# fp_banana.net
KiCad netlist of a schematic drawn in EAGLE
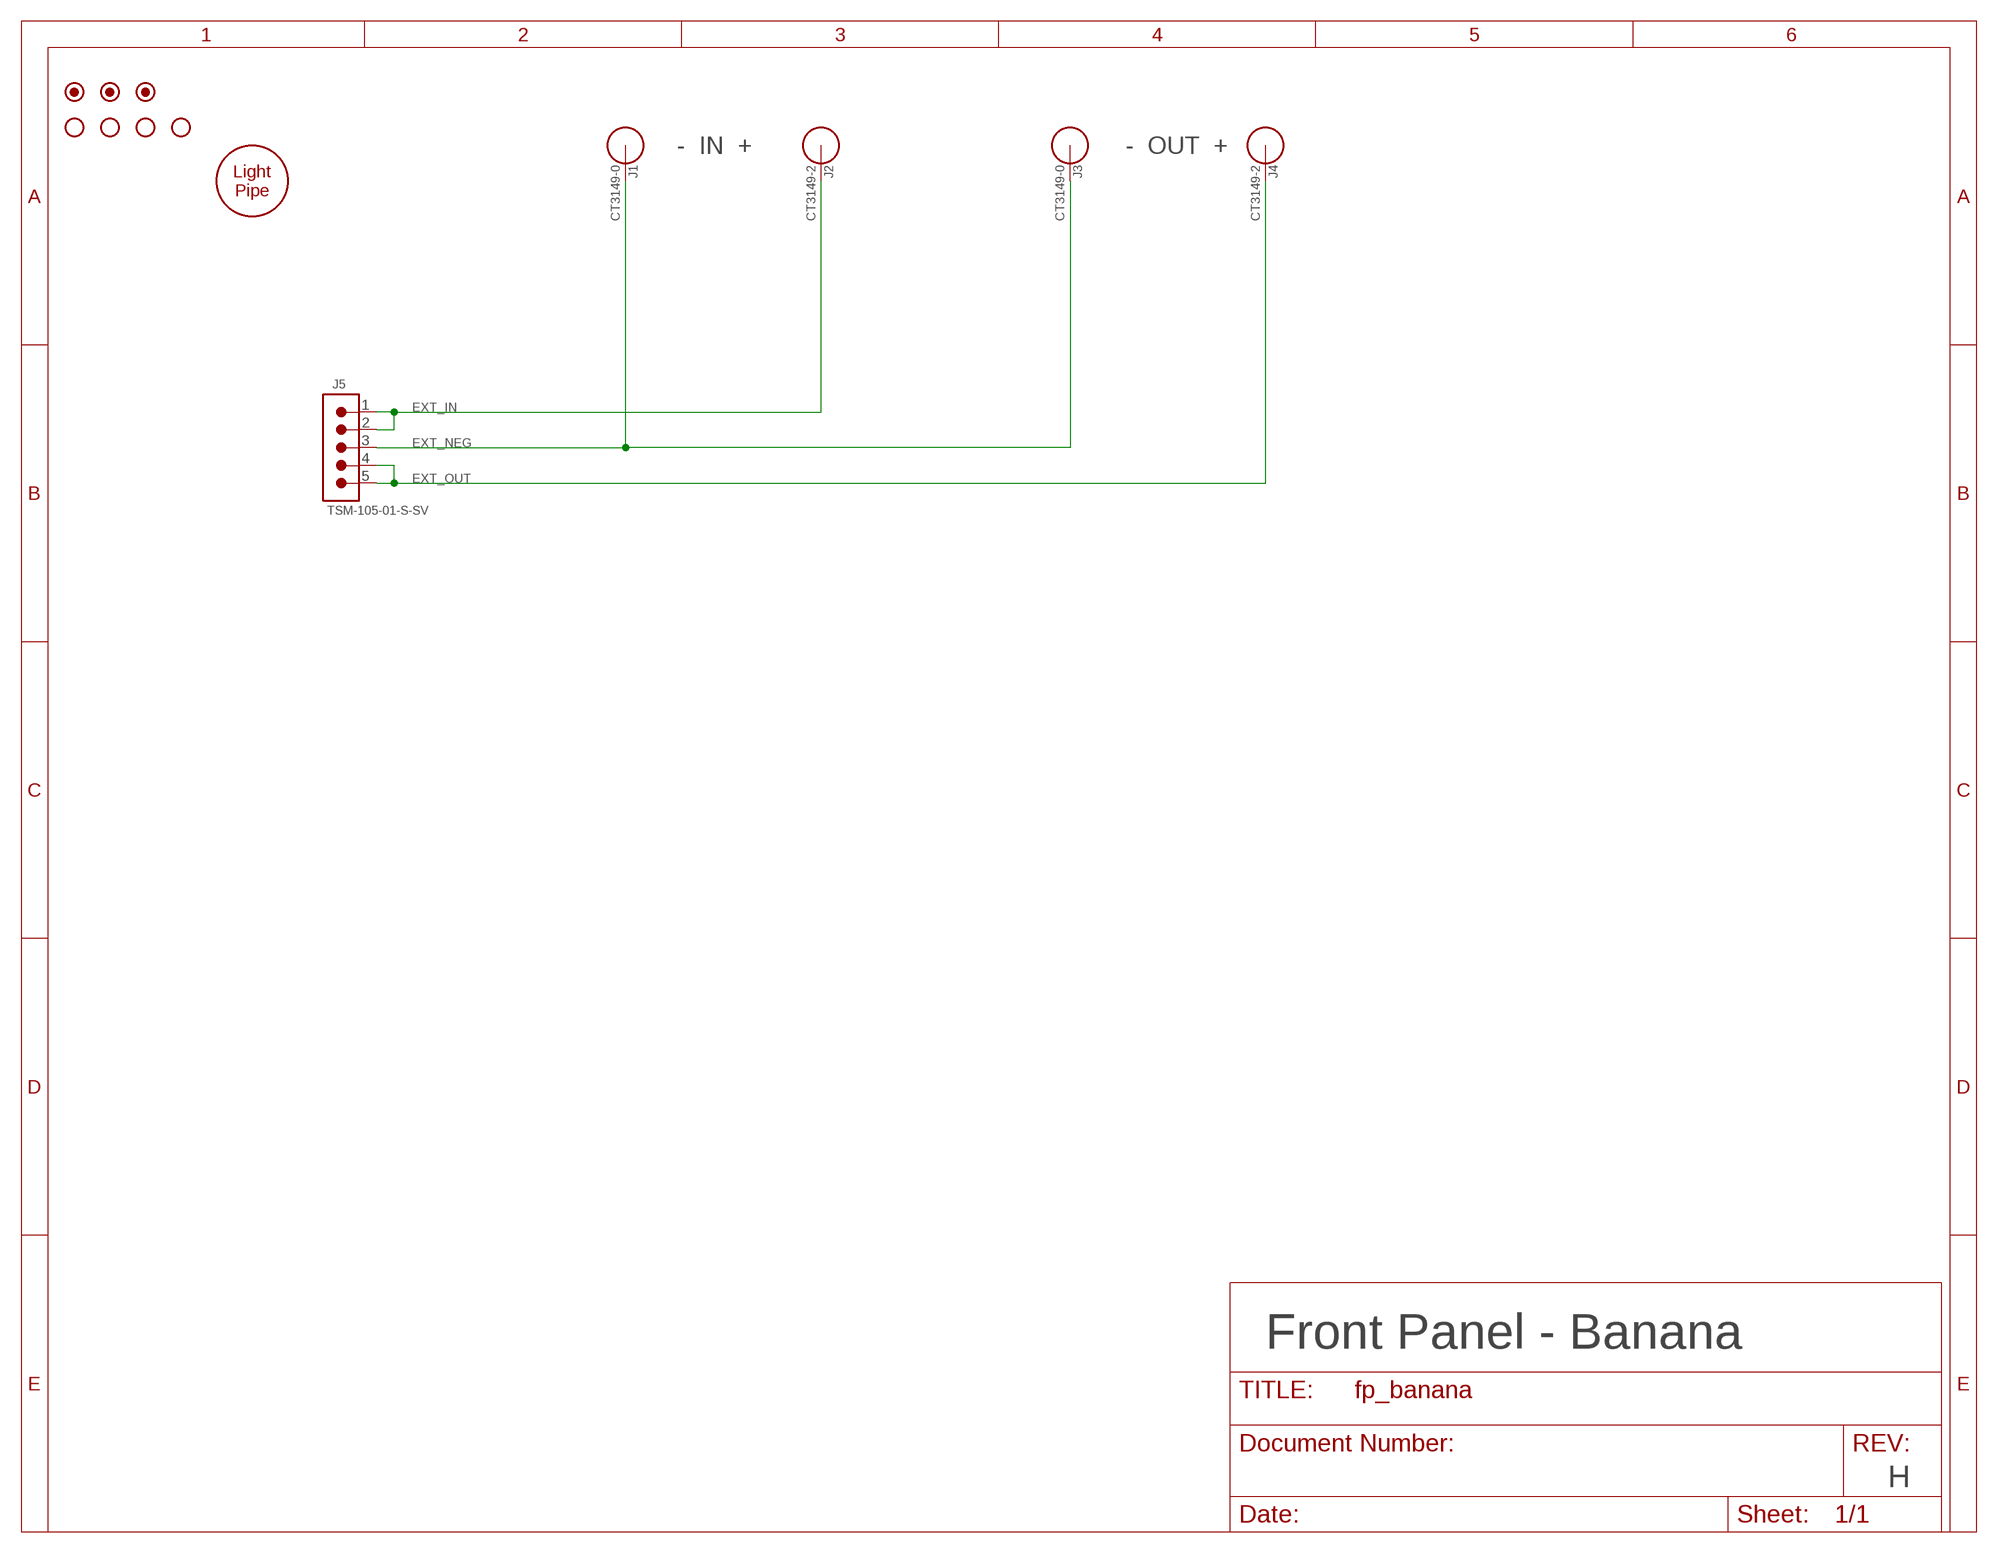
[diagram p0: schematic, sheet 1]

(export (version "E")
  (design (tool "Eeschema 10.0.6"))
  (components
    (comp (ref "FUD1")
      (value "FIDUCIAL_1MM")
      (footprint "eagle-import:FIDUCIAL_1MM_2MM")
      (libsource (lib "eagle-import") (part "FIDUCIAL_1MM"))
    )
    (comp (ref "FUD2")
      (value "FIDUCIAL_1MM")
      (footprint "eagle-import:FIDUCIAL_1MM_2MM")
      (libsource (lib "eagle-import") (part "FIDUCIAL_1MM"))
    )
    (comp (ref "FUD3")
      (value "FIDUCIAL_1MM")
      (footprint "eagle-import:FIDUCIAL_1MM_2MM")
      (libsource (lib "eagle-import") (part "FIDUCIAL_1MM"))
    )
    (comp (ref "H1")
      (value "51513020125F")
      (footprint "eagle-import:LP_3MM")
      (fields (field (name "MPN") "51513020125F"))
      (libsource (lib "eagle-import") (part "LIGHT_PIPE_PANEL_3MM"))
    )
    (comp (ref "H2")
      (value "HOLE_#6")
      (footprint "eagle-import:HOLE_3.5MM")
      (libsource (lib "eagle-import") (part "HOLE_#6"))
    )
    (comp (ref "H3")
      (value "HOLE_#6")
      (footprint "eagle-import:HOLE_3.5MM")
      (libsource (lib "eagle-import") (part "HOLE_#6"))
    )
    (comp (ref "H4")
      (value "HOLE_#6")
      (footprint "eagle-import:HOLE_3.5MM")
      (libsource (lib "eagle-import") (part "HOLE_#6"))
    )
    (comp (ref "H5")
      (value "HOLE_#6")
      (footprint "eagle-import:HOLE_3.5MM")
      (libsource (lib "eagle-import") (part "HOLE_#6"))
    )
    (comp (ref "J1")
      (value "CT3149-0")
      (footprint "eagle-import:CT3149")
      (libsource (lib "eagle-import") (part "BANANA-JACK_CT3149"))
    )
    (comp (ref "J2")
      (value "CT3149-2")
      (footprint "eagle-import:CT3149")
      (libsource (lib "eagle-import") (part "BANANA-JACK_CT3149"))
    )
    (comp (ref "J3")
      (value "CT3149-0")
      (footprint "eagle-import:CT3149")
      (libsource (lib "eagle-import") (part "BANANA-JACK_CT3149"))
    )
    (comp (ref "J4")
      (value "CT3149-2")
      (footprint "eagle-import:CT3149")
      (libsource (lib "eagle-import") (part "BANANA-JACK_CT3149"))
    )
    (comp (ref "J5")
      (value "TSM-105-01-S-SV")
      (footprint "eagle-import:CONN_0.1_5X1_MS")
      (libsource (lib "eagle-import") (part "CONN_0.1_5X1_MS"))
    )
  )
  (nets
    (net (code "1") (name "/EXT_IN") (class "Default")
      (node (ref "J2") (pin "A") (pinfunction "1_A") (pintype "bidirectional"))
      (node (ref "J5") (pin "1") (pinfunction "1_1") (pintype "bidirectional"))
      (node (ref "J5") (pin "2") (pinfunction "2_2") (pintype "bidirectional"))
    )
    (net (code "2") (name "/EXT_NEG") (class "Default")
      (node (ref "J1") (pin "A") (pinfunction "1_A") (pintype "bidirectional"))
      (node (ref "J3") (pin "A") (pinfunction "1_A") (pintype "bidirectional"))
      (node (ref "J5") (pin "3") (pinfunction "3_3") (pintype "bidirectional"))
    )
    (net (code "3") (name "/EXT_OUT") (class "Default")
      (node (ref "J4") (pin "A") (pinfunction "1_A") (pintype "bidirectional"))
      (node (ref "J5") (pin "4") (pinfunction "4_4") (pintype "bidirectional"))
      (node (ref "J5") (pin "5") (pinfunction "5_5") (pintype "bidirectional"))
    )
  )
)
